# SERVODENGEN_ver2.net
KiCad netlist of a schematic drawn in EAGLE
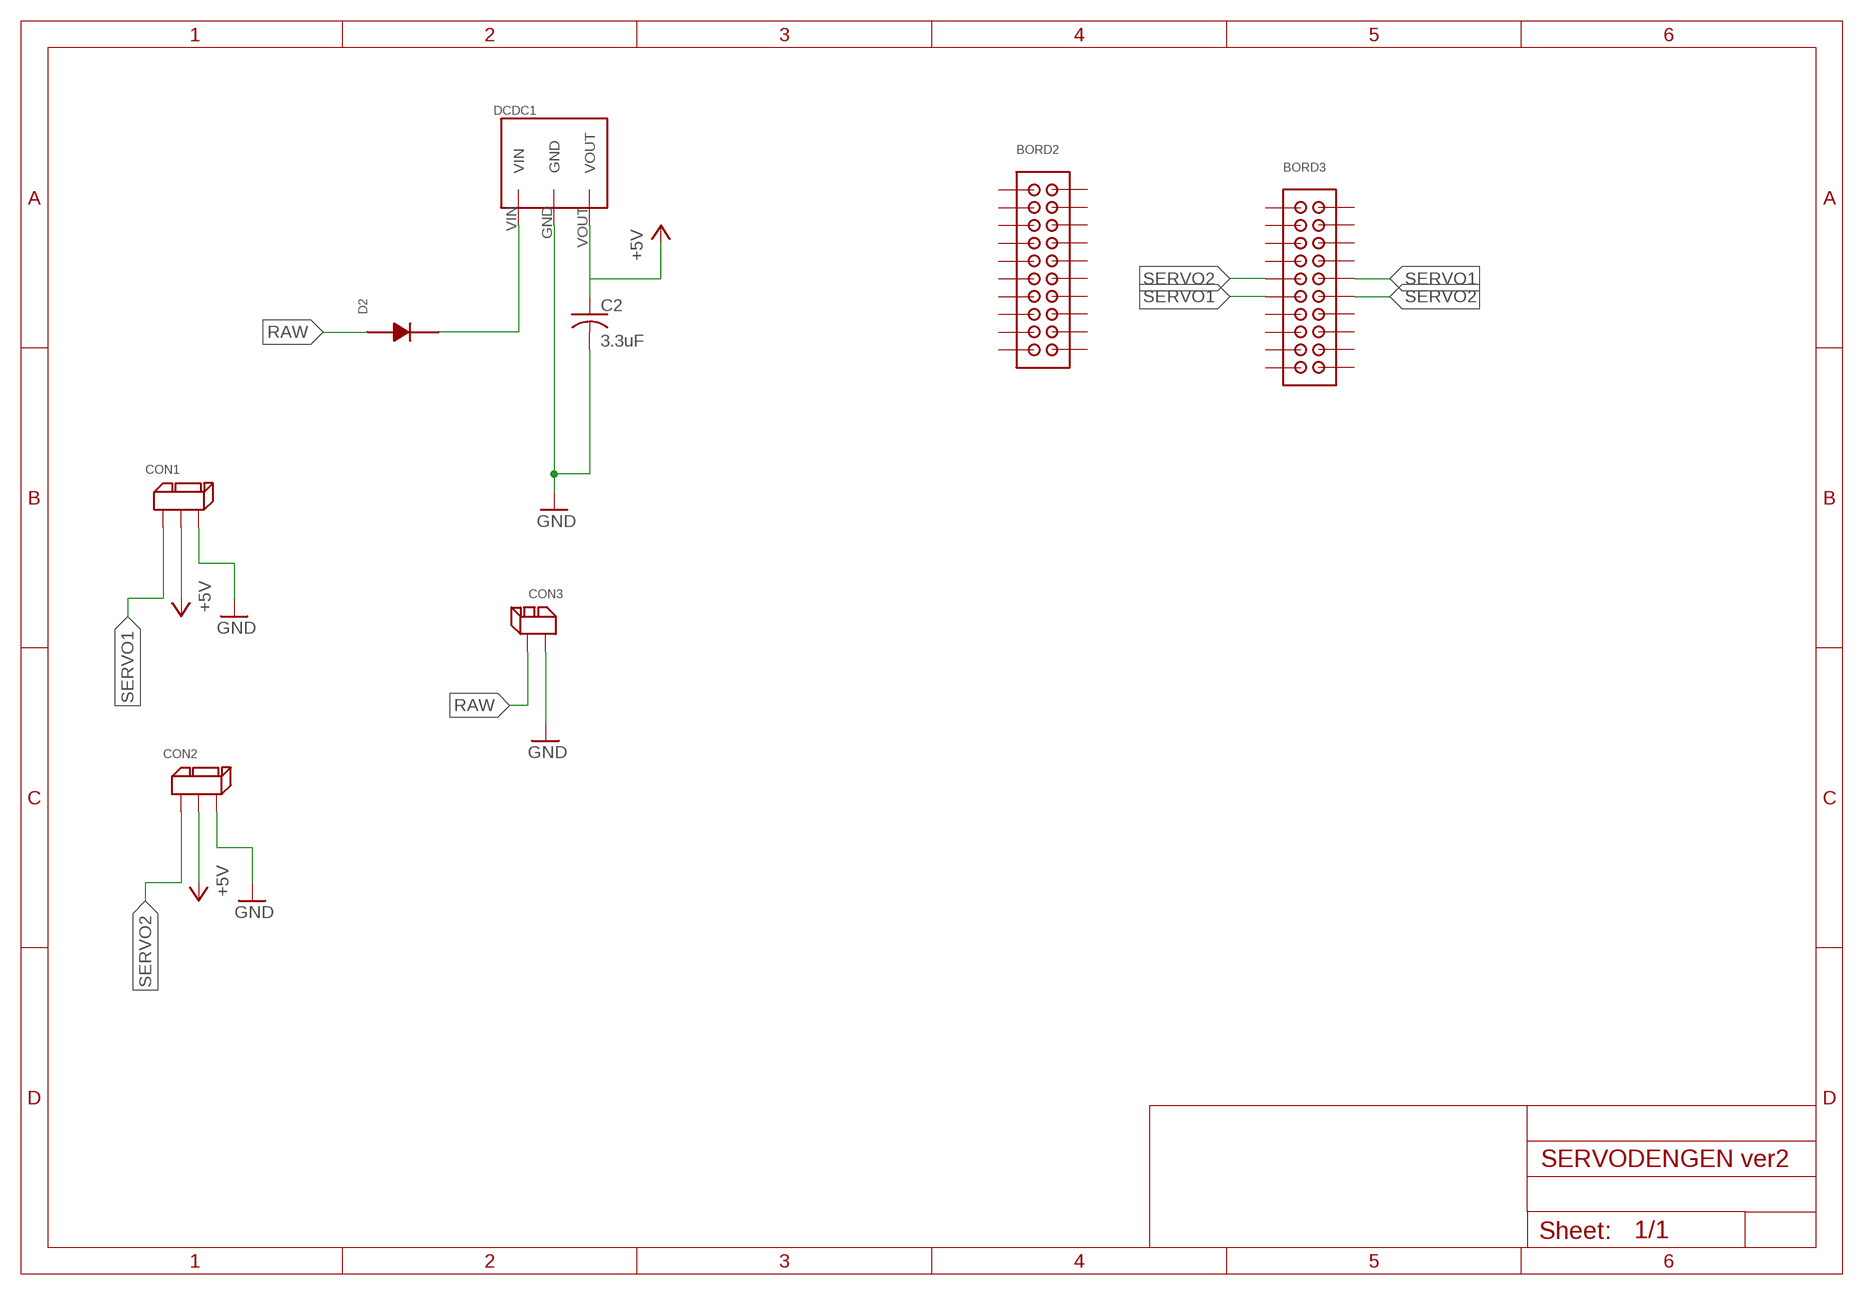
[diagram p0: schematic, sheet 1]

(export (version "E")
  (design (tool "Eeschema 10.0.6"))
  (components
    (comp (ref "BORD2")
      (value "2X10")
      (footprint "eagle-import:2X10")
      (libsource (lib "eagle-import") (part "2X10"))
    )
    (comp (ref "BORD3")
      (value "2X10")
      (footprint "eagle-import:2X10")
      (libsource (lib "eagle-import") (part "2X10"))
    )
    (comp (ref "C2")
      (value "3.3uF")
      (footprint "eagle-import:C0603")
      (libsource (lib "eagle-import") (part "C-USC0603"))
    )
    (comp (ref "CON1")
      (value "3PIN")
      (footprint "eagle-import:3PIN")
      (libsource (lib "eagle-import") (part "3PIN"))
    )
    (comp (ref "CON2")
      (value "3PIN")
      (footprint "eagle-import:3PIN")
      (libsource (lib "eagle-import") (part "3PIN"))
    )
    (comp (ref "CON3")
      (value "2PIN")
      (footprint "eagle-import:2PIN")
      (libsource (lib "eagle-import") (part "2PIN"))
    )
    (comp (ref "D2")
      (value "1W4148W")
      (footprint "eagle-import:SOD-123")
      (libsource (lib "eagle-import") (part "1W4148W"))
    )
    (comp (ref "DCDC1")
      (value "5V1A_M78AR05-1")
      (footprint "eagle-import:5V1A_M78AR05-1")
      (libsource (lib "eagle-import") (part "5V1A_M78AR05-1"))
    )
  )
  (nets
    (net (code "1") (name "+5V") (class "Default")
      (node (ref "C2") (pin "1") (pinfunction "1_1") (pintype "passive"))
      (node (ref "CON1") (pin "P$2") (pinfunction "P$2_P$2") (pintype "bidirectional"))
      (node (ref "CON2") (pin "P$2") (pinfunction "P$2_P$2") (pintype "bidirectional"))
      (node (ref "DCDC1") (pin "VOUT") (pinfunction "VOUT_VOUT") (pintype "bidirectional"))
    )
    (net (code "2") (name "GND") (class "Default")
      (node (ref "C2") (pin "2") (pinfunction "2_2") (pintype "passive"))
      (node (ref "CON1") (pin "P$3") (pinfunction "P$3_P$3") (pintype "bidirectional"))
      (node (ref "CON2") (pin "P$3") (pinfunction "P$3_P$3") (pintype "bidirectional"))
      (node (ref "CON3") (pin "P$1") (pinfunction "P$1_P$1") (pintype "bidirectional"))
      (node (ref "DCDC1") (pin "GND") (pinfunction "GND_GND") (pintype "bidirectional"))
    )
    (net (code "3") (name "RAW") (class "Default")
      (node (ref "CON3") (pin "P$2") (pinfunction "P$2_P$2") (pintype "bidirectional"))
      (node (ref "D2") (pin "A") (pinfunction "A_A") (pintype "bidirectional"))
      (node (ref "DCDC1") (pin "VIN") (pinfunction "VIN_VIN") (pintype "bidirectional"))
    )
    (net (code "4") (name "SERVO1") (class "Default")
      (node (ref "BORD3") (pin "P$10") (pinfunction "P$10_P$10") (pintype "bidirectional"))
      (node (ref "BORD3") (pin "P$11") (pinfunction "P$11_P$11") (pintype "bidirectional"))
      (node (ref "CON1") (pin "P$1") (pinfunction "P$1_P$1") (pintype "bidirectional"))
    )
    (net (code "5") (name "SERVO2") (class "Default")
      (node (ref "BORD3") (pin "P$12") (pinfunction "P$12_P$12") (pintype "bidirectional"))
      (node (ref "BORD3") (pin "P$9") (pinfunction "P$9_P$9") (pintype "bidirectional"))
      (node (ref "CON2") (pin "P$1") (pinfunction "P$1_P$1") (pintype "bidirectional"))
    )
    (net (code "6") (name "unconnected-(BORD2-PadP$1)") (class "Default")
      (node (ref "BORD2") (pin "P$1") (pinfunction "P$1_P$1") (pintype "bidirectional"))
    )
    (net (code "7") (name "unconnected-(BORD2-PadP$2)") (class "Default")
      (node (ref "BORD2") (pin "P$2") (pinfunction "P$2_P$2") (pintype "bidirectional"))
    )
    (net (code "8") (name "unconnected-(BORD2-PadP$3)") (class "Default")
      (node (ref "BORD2") (pin "P$3") (pinfunction "P$3_P$3") (pintype "bidirectional"))
    )
    (net (code "9") (name "unconnected-(BORD2-PadP$4)") (class "Default")
      (node (ref "BORD2") (pin "P$4") (pinfunction "P$4_P$4") (pintype "bidirectional"))
    )
    (net (code "10") (name "unconnected-(BORD2-PadP$5)") (class "Default")
      (node (ref "BORD2") (pin "P$5") (pinfunction "P$5_P$5") (pintype "bidirectional"))
    )
    (net (code "11") (name "unconnected-(BORD2-PadP$6)") (class "Default")
      (node (ref "BORD2") (pin "P$6") (pinfunction "P$6_P$6") (pintype "bidirectional"))
    )
    (net (code "12") (name "unconnected-(BORD2-PadP$7)") (class "Default")
      (node (ref "BORD2") (pin "P$7") (pinfunction "P$7_P$7") (pintype "bidirectional"))
    )
    (net (code "13") (name "unconnected-(BORD2-PadP$8)") (class "Default")
      (node (ref "BORD2") (pin "P$8") (pinfunction "P$8_P$8") (pintype "bidirectional"))
    )
    (net (code "14") (name "unconnected-(BORD2-PadP$9)") (class "Default")
      (node (ref "BORD2") (pin "P$9") (pinfunction "P$9_P$9") (pintype "bidirectional"))
    )
    (net (code "15") (name "unconnected-(BORD2-PadP$10)") (class "Default")
      (node (ref "BORD2") (pin "P$10") (pinfunction "P$10_P$10") (pintype "bidirectional"))
    )
    (net (code "16") (name "unconnected-(BORD2-PadP$11)") (class "Default")
      (node (ref "BORD2") (pin "P$11") (pinfunction "P$11_P$11") (pintype "bidirectional"))
    )
    (net (code "17") (name "unconnected-(BORD2-PadP$12)") (class "Default")
      (node (ref "BORD2") (pin "P$12") (pinfunction "P$12_P$12") (pintype "bidirectional"))
    )
    (net (code "18") (name "unconnected-(BORD2-PadP$13)") (class "Default")
      (node (ref "BORD2") (pin "P$13") (pinfunction "P$13_P$13") (pintype "bidirectional"))
    )
    (net (code "19") (name "unconnected-(BORD2-PadP$14)") (class "Default")
      (node (ref "BORD2") (pin "P$14") (pinfunction "P$14_P$14") (pintype "bidirectional"))
    )
    (net (code "20") (name "unconnected-(BORD2-PadP$15)") (class "Default")
      (node (ref "BORD2") (pin "P$15") (pinfunction "P$15_P$15") (pintype "bidirectional"))
    )
    (net (code "21") (name "unconnected-(BORD2-PadP$16)") (class "Default")
      (node (ref "BORD2") (pin "P$16") (pinfunction "P$16_P$16") (pintype "bidirectional"))
    )
    (net (code "22") (name "unconnected-(BORD2-PadP$17)") (class "Default")
      (node (ref "BORD2") (pin "P$17") (pinfunction "P$17_P$17") (pintype "bidirectional"))
    )
    (net (code "23") (name "unconnected-(BORD2-PadP$18)") (class "Default")
      (node (ref "BORD2") (pin "P$18") (pinfunction "P$18_P$18") (pintype "bidirectional"))
    )
    (net (code "24") (name "unconnected-(BORD2-PadP$19)") (class "Default")
      (node (ref "BORD2") (pin "P$19") (pinfunction "P$19_P$19") (pintype "bidirectional"))
    )
    (net (code "25") (name "unconnected-(BORD2-PadP$20)") (class "Default")
      (node (ref "BORD2") (pin "P$20") (pinfunction "P$20_P$20") (pintype "bidirectional"))
    )
    (net (code "26") (name "unconnected-(BORD3-PadP$1)") (class "Default")
      (node (ref "BORD3") (pin "P$1") (pinfunction "P$1_P$1") (pintype "bidirectional"))
    )
    (net (code "27") (name "unconnected-(BORD3-PadP$2)") (class "Default")
      (node (ref "BORD3") (pin "P$2") (pinfunction "P$2_P$2") (pintype "bidirectional"))
    )
    (net (code "28") (name "unconnected-(BORD3-PadP$3)") (class "Default")
      (node (ref "BORD3") (pin "P$3") (pinfunction "P$3_P$3") (pintype "bidirectional"))
    )
    (net (code "29") (name "unconnected-(BORD3-PadP$4)") (class "Default")
      (node (ref "BORD3") (pin "P$4") (pinfunction "P$4_P$4") (pintype "bidirectional"))
    )
    (net (code "30") (name "unconnected-(BORD3-PadP$5)") (class "Default")
      (node (ref "BORD3") (pin "P$5") (pinfunction "P$5_P$5") (pintype "bidirectional"))
    )
    (net (code "31") (name "unconnected-(BORD3-PadP$6)") (class "Default")
      (node (ref "BORD3") (pin "P$6") (pinfunction "P$6_P$6") (pintype "bidirectional"))
    )
    (net (code "32") (name "unconnected-(BORD3-PadP$7)") (class "Default")
      (node (ref "BORD3") (pin "P$7") (pinfunction "P$7_P$7") (pintype "bidirectional"))
    )
    (net (code "33") (name "unconnected-(BORD3-PadP$8)") (class "Default")
      (node (ref "BORD3") (pin "P$8") (pinfunction "P$8_P$8") (pintype "bidirectional"))
    )
    (net (code "34") (name "unconnected-(BORD3-PadP$13)") (class "Default")
      (node (ref "BORD3") (pin "P$13") (pinfunction "P$13_P$13") (pintype "bidirectional"))
    )
    (net (code "35") (name "unconnected-(BORD3-PadP$14)") (class "Default")
      (node (ref "BORD3") (pin "P$14") (pinfunction "P$14_P$14") (pintype "bidirectional"))
    )
    (net (code "36") (name "unconnected-(BORD3-PadP$15)") (class "Default")
      (node (ref "BORD3") (pin "P$15") (pinfunction "P$15_P$15") (pintype "bidirectional"))
    )
    (net (code "37") (name "unconnected-(BORD3-PadP$16)") (class "Default")
      (node (ref "BORD3") (pin "P$16") (pinfunction "P$16_P$16") (pintype "bidirectional"))
    )
    (net (code "38") (name "unconnected-(BORD3-PadP$17)") (class "Default")
      (node (ref "BORD3") (pin "P$17") (pinfunction "P$17_P$17") (pintype "bidirectional"))
    )
    (net (code "39") (name "unconnected-(BORD3-PadP$18)") (class "Default")
      (node (ref "BORD3") (pin "P$18") (pinfunction "P$18_P$18") (pintype "bidirectional"))
    )
    (net (code "40") (name "unconnected-(BORD3-PadP$19)") (class "Default")
      (node (ref "BORD3") (pin "P$19") (pinfunction "P$19_P$19") (pintype "bidirectional"))
    )
    (net (code "41") (name "unconnected-(BORD3-PadP$20)") (class "Default")
      (node (ref "BORD3") (pin "P$20") (pinfunction "P$20_P$20") (pintype "bidirectional"))
    )
    (net (code "42") (name "unconnected-(D2-PadC)") (class "Default")
      (node (ref "D2") (pin "C") (pinfunction "C_C") (pintype "bidirectional"))
    )
  )
)
